# mcu_v03.net
KiCad netlist of a schematic drawn in EAGLE
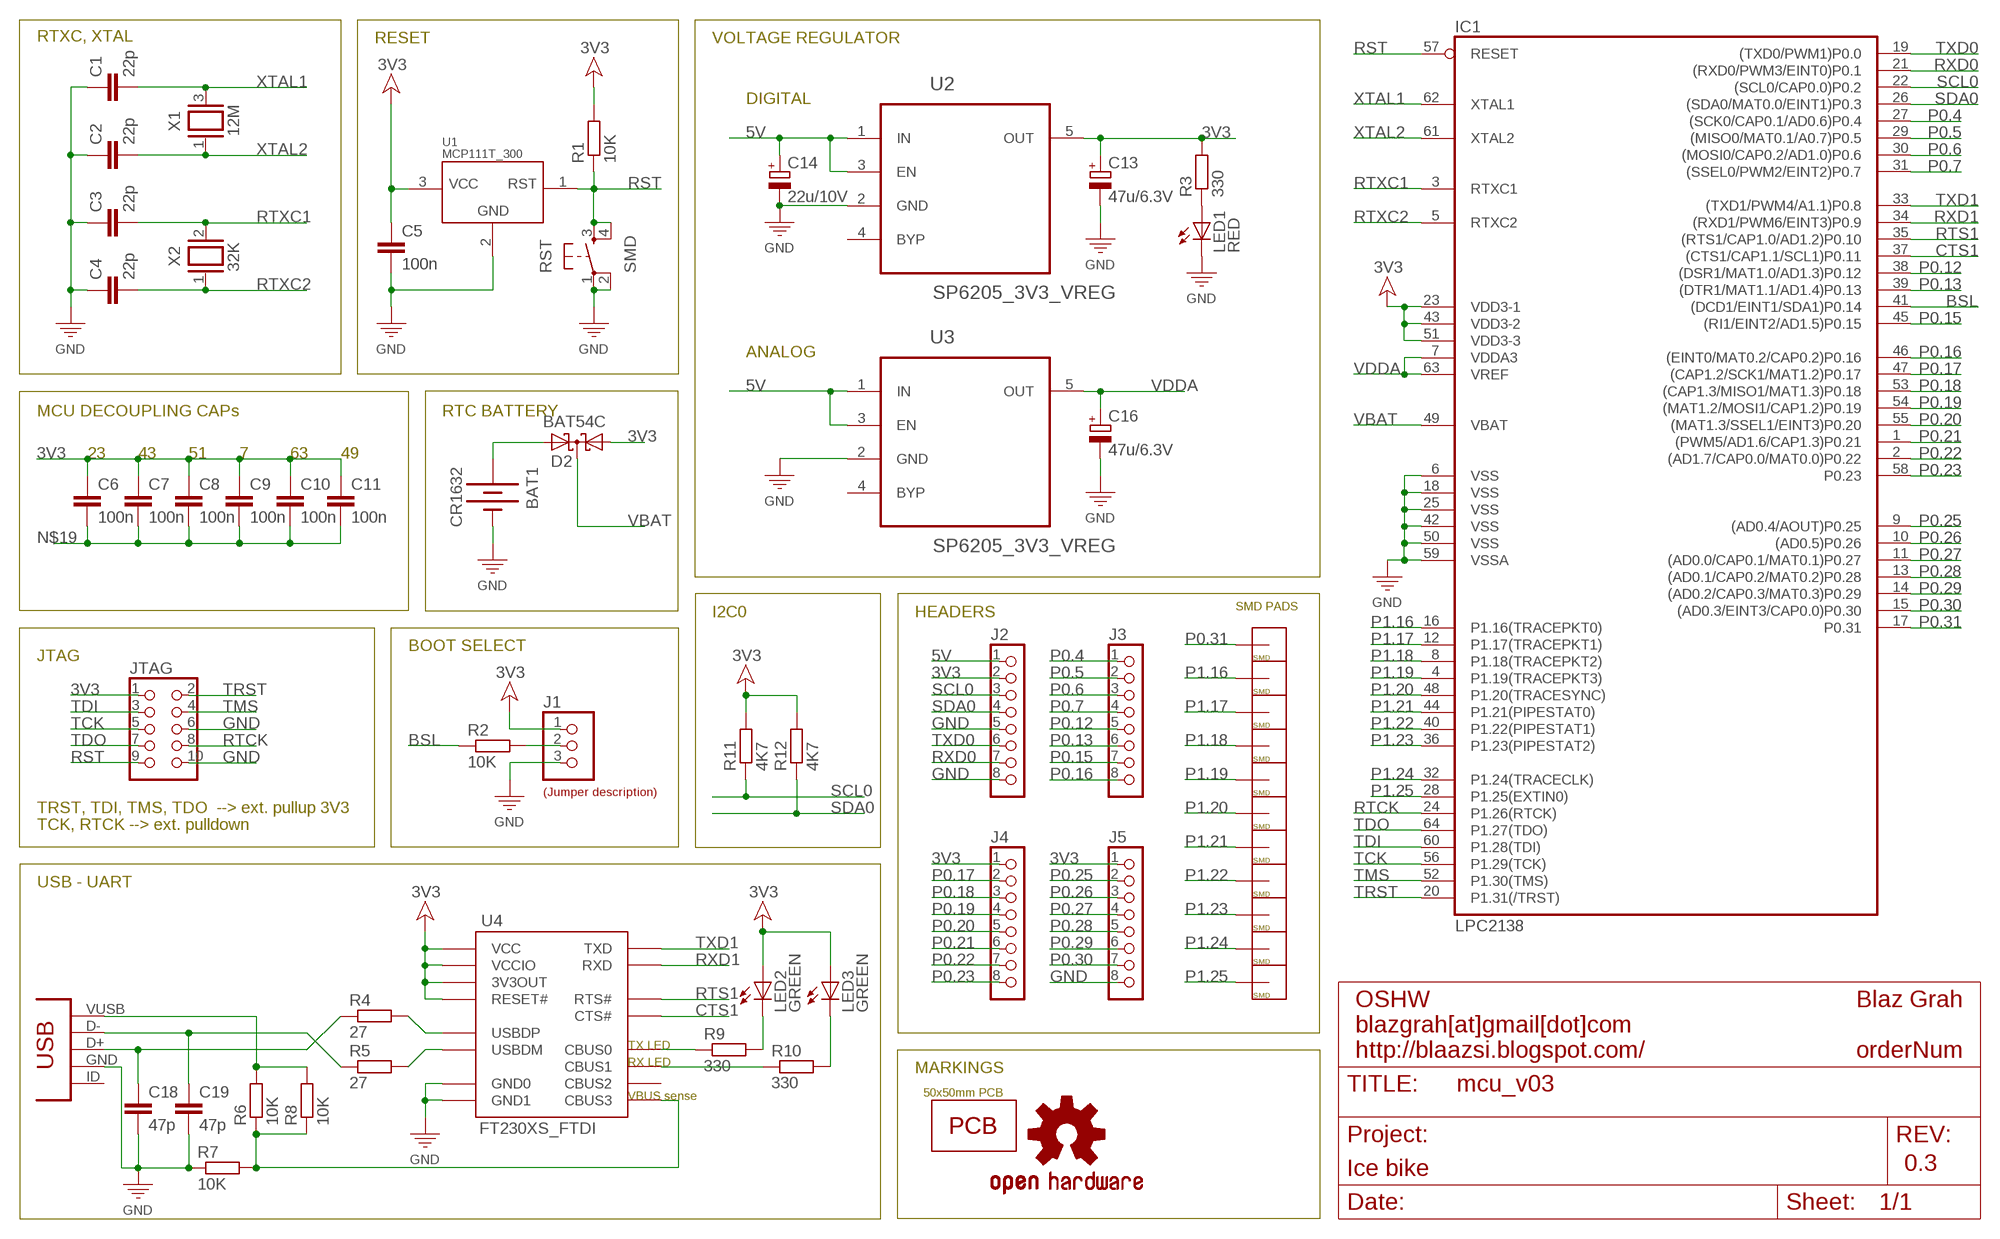
[diagram p0: schematic, sheet 1]

(export (version "E")
  (design (tool "Eeschema 10.0.6"))
  (components
    (comp (ref "BAT1")
      (value "CR1632")
      (footprint "eagle-import:BATTERY_16MM_SDM")
      (libsource (lib "eagle-import") (part "BATTERY"))
    )
    (comp (ref "C1")
      (value "22p")
      (footprint "eagle-import:C0603")
      (libsource (lib "eagle-import") (part "C-EUC0603"))
    )
    (comp (ref "C2")
      (value "22p")
      (footprint "eagle-import:C0603")
      (libsource (lib "eagle-import") (part "C-EUC0603"))
    )
    (comp (ref "C3")
      (value "22p")
      (footprint "eagle-import:C0603")
      (libsource (lib "eagle-import") (part "C-EUC0603"))
    )
    (comp (ref "C4")
      (value "22p")
      (footprint "eagle-import:C0603")
      (libsource (lib "eagle-import") (part "C-EUC0603"))
    )
    (comp (ref "C5")
      (value "100n")
      (footprint "eagle-import:C0603")
      (libsource (lib "eagle-import") (part "C-EUC0603"))
    )
    (comp (ref "C6")
      (value "100n")
      (footprint "eagle-import:C0603")
      (libsource (lib "eagle-import") (part "C-EUC0603"))
    )
    (comp (ref "C7")
      (value "100n")
      (footprint "eagle-import:C0603")
      (libsource (lib "eagle-import") (part "C-EUC0603"))
    )
    (comp (ref "C8")
      (value "100n")
      (footprint "eagle-import:C0603")
      (libsource (lib "eagle-import") (part "C-EUC0603"))
    )
    (comp (ref "C9")
      (value "100n")
      (footprint "eagle-import:C0603")
      (libsource (lib "eagle-import") (part "C-EUC0603"))
    )
    (comp (ref "C10")
      (value "100n")
      (footprint "eagle-import:C0603")
      (libsource (lib "eagle-import") (part "C-EUC0603"))
    )
    (comp (ref "C11")
      (value "100n")
      (footprint "eagle-import:C0603")
      (libsource (lib "eagle-import") (part "C-EUC0603"))
    )
    (comp (ref "C13")
      (value "47u/6.3V")
      (footprint "eagle-import:SMC_B")
      (libsource (lib "eagle-import") (part "CAPACITOR_POL-SMC_B"))
    )
    (comp (ref "C14")
      (value "22u/10V")
      (footprint "eagle-import:SMC_B")
      (libsource (lib "eagle-import") (part "CAPACITOR_POL-SMC_B"))
    )
    (comp (ref "C16")
      (value "47u/6.3V")
      (footprint "eagle-import:SMC_B")
      (libsource (lib "eagle-import") (part "CAPACITOR_POL-SMC_B"))
    )
    (comp (ref "C18")
      (value "47p")
      (footprint "eagle-import:C0603")
      (libsource (lib "eagle-import") (part "C-EUC0603"))
    )
    (comp (ref "C19")
      (value "47p")
      (footprint "eagle-import:C0603")
      (libsource (lib "eagle-import") (part "C-EUC0603"))
    )
    (comp (ref "D2")
      (value "BAT54C")
      (footprint "eagle-import:SOT23")
      (libsource (lib "eagle-import") (part "BAT54C"))
    )
    (comp (ref "IC1")
      (value "LPC2138")
      (footprint "eagle-import:LQFP64")
      (libsource (lib "eagle-import") (part "LCP2138_LQFP64"))
    )
    (comp (ref "J1")
      (value "JUMPER_1X3ALT")
      (footprint "eagle-import:JUMPER_SOLDER")
      (libsource (lib "eagle-import") (part "JUMPER_1X3ALT"))
    )
    (comp (ref "J2")
      (value "CON_HEADER_1X08-PTH")
      (footprint "eagle-import:M1X8")
      (libsource (lib "eagle-import") (part "CON_HEADER_1X08-PTH"))
    )
    (comp (ref "J3")
      (value "CON_HEADER_1X08-PTH")
      (footprint "eagle-import:M1X8")
      (libsource (lib "eagle-import") (part "CON_HEADER_1X08-PTH"))
    )
    (comp (ref "J4")
      (value "CON_HEADER_1X08-PTH")
      (footprint "eagle-import:M1X8")
      (libsource (lib "eagle-import") (part "CON_HEADER_1X08-PTH"))
    )
    (comp (ref "J5")
      (value "CON_HEADER_1X08-PTH")
      (footprint "eagle-import:M1X8")
      (libsource (lib "eagle-import") (part "CON_HEADER_1X08-PTH"))
    )
    (comp (ref "JTAG")
      (value "CON_HEADER_2X05-PTH+SHROUDED_A")
      (footprint "eagle-import:PINSHRD_PTH_2X05")
      (libsource (lib "eagle-import") (part "CON_HEADER_2X05-PTH+SHROUDED_A"))
    )
    (comp (ref "LED1")
      (value "RED")
      (footprint "eagle-import:LED-0603")
      (libsource (lib "eagle-import") (part "LED0603"))
    )
    (comp (ref "LED2")
      (value "GREEN")
      (footprint "eagle-import:LED-0603")
      (libsource (lib "eagle-import") (part "LED0603"))
    )
    (comp (ref "LED3")
      (value "GREEN")
      (footprint "eagle-import:LED-0603")
      (libsource (lib "eagle-import") (part "LED0603"))
    )
    (comp (ref "PCB1")
      (value "PCB_DP_SQUARE-5X5")
      (footprint "eagle-import:PCB5X5")
      (libsource (lib "eagle-import") (part "PCB_DP_SQUARE-5X5"))
    )
    (comp (ref "R1")
      (value "10K")
      (footprint "eagle-import:R0603")
      (libsource (lib "eagle-import") (part "R-EU0603"))
    )
    (comp (ref "R2")
      (value "10K")
      (footprint "eagle-import:R0603")
      (libsource (lib "eagle-import") (part "R-EU0603"))
    )
    (comp (ref "R3")
      (value "330")
      (footprint "eagle-import:R0603")
      (libsource (lib "eagle-import") (part "R-EU0603"))
    )
    (comp (ref "R4")
      (value "27")
      (footprint "eagle-import:R0603")
      (libsource (lib "eagle-import") (part "R-EU0603"))
    )
    (comp (ref "R5")
      (value "27")
      (footprint "eagle-import:R0603")
      (libsource (lib "eagle-import") (part "R-EU0603"))
    )
    (comp (ref "R6")
      (value "10K")
      (footprint "eagle-import:R0603")
      (libsource (lib "eagle-import") (part "R-EU0603"))
    )
    (comp (ref "R7")
      (value "10K")
      (footprint "eagle-import:R0603")
      (libsource (lib "eagle-import") (part "R-EU0603"))
    )
    (comp (ref "R8")
      (value "10K")
      (footprint "eagle-import:R0603")
      (libsource (lib "eagle-import") (part "R-EU0603"))
    )
    (comp (ref "R9")
      (value "330")
      (footprint "eagle-import:R0603")
      (libsource (lib "eagle-import") (part "R-EU0603"))
    )
    (comp (ref "R10")
      (value "330")
      (footprint "eagle-import:R0603")
      (libsource (lib "eagle-import") (part "R-EU0603"))
    )
    (comp (ref "R11")
      (value "4K7")
      (footprint "eagle-import:R0603")
      (libsource (lib "eagle-import") (part "R-EU0603"))
    )
    (comp (ref "R12")
      (value "4K7")
      (footprint "eagle-import:R0603")
      (libsource (lib "eagle-import") (part "R-EU0603"))
    )
    (comp (ref "RST")
      (value "SMD")
      (footprint "eagle-import:BUTTON_SW_4P_SMD")
      (libsource (lib "eagle-import") (part "TACTIL_BUTTON"))
    )
    (comp (ref "U$11")
      (value "LABEL_JUMPER_1X3")
      (footprint "eagle-import:JUMP3_DESC")
      (fields (field (name "LEFT") "USER") (field (name "RIGHT") "BOOT"))
      (libsource (lib "eagle-import") (part "LABEL_JUMPER_1X3"))
    )
    (comp (ref "U$13")
      (value "FRAME_DINA4_L")
      (footprint "eagle-import:DP_LOGO")
      (fields
        (field (name "AUTHOR") "Blaz Grah")
        (field (name "LICENSE") "OSHW")
        (field (name "PROJECT") "Ice bike")
        (field (name "REV") "0.3")
        (field (name "URL1") "blazgrah[at]gmail[dot]com")
        (field (name "URL2") "http://blaazsi.blogspot.com/")
      )
      (libsource (lib "eagle-import") (part "FRAME_DINA4_L"))
    )
    (comp (ref "U$17")
      (value "OSHW-LOGOS")
      (footprint "eagle-import:OSHW-LOGO-S")
      (libsource (lib "eagle-import") (part "OSHW-LOGOS"))
    )
    (comp (ref "U$28")
      (value "CON_SMD_PAD_1X1")
      (footprint "eagle-import:CON_SMD_PAD_1_")
      (libsource (lib "eagle-import") (part "CON_SMD_PAD_1X1"))
    )
    (comp (ref "U$29")
      (value "CON_SMD_PAD_1X1")
      (footprint "eagle-import:CON_SMD_PAD_1_")
      (libsource (lib "eagle-import") (part "CON_SMD_PAD_1X1"))
    )
    (comp (ref "U$30")
      (value "CON_SMD_PAD_1X1")
      (footprint "eagle-import:CON_SMD_PAD_1_")
      (libsource (lib "eagle-import") (part "CON_SMD_PAD_1X1"))
    )
    (comp (ref "U$31")
      (value "CON_SMD_PAD_1X1")
      (footprint "eagle-import:CON_SMD_PAD_1_")
      (libsource (lib "eagle-import") (part "CON_SMD_PAD_1X1"))
    )
    (comp (ref "U$32")
      (value "CON_SMD_PAD_1X1")
      (footprint "eagle-import:CON_SMD_PAD_1_")
      (libsource (lib "eagle-import") (part "CON_SMD_PAD_1X1"))
    )
    (comp (ref "U$33")
      (value "CON_SMD_PAD_1X1")
      (footprint "eagle-import:CON_SMD_PAD_1_")
      (libsource (lib "eagle-import") (part "CON_SMD_PAD_1X1"))
    )
    (comp (ref "U$34")
      (value "CON_SMD_PAD_1X1")
      (footprint "eagle-import:CON_SMD_PAD_1_")
      (libsource (lib "eagle-import") (part "CON_SMD_PAD_1X1"))
    )
    (comp (ref "U$35")
      (value "CON_SMD_PAD_1X1")
      (footprint "eagle-import:CON_SMD_PAD_1_")
      (libsource (lib "eagle-import") (part "CON_SMD_PAD_1X1"))
    )
    (comp (ref "U$36")
      (value "CON_SMD_PAD_1X1")
      (footprint "eagle-import:CON_SMD_PAD_1_")
      (libsource (lib "eagle-import") (part "CON_SMD_PAD_1X1"))
    )
    (comp (ref "U$37")
      (value "CON_SMD_PAD_1X1")
      (footprint "eagle-import:CON_SMD_PAD_1_")
      (libsource (lib "eagle-import") (part "CON_SMD_PAD_1X1"))
    )
    (comp (ref "U$38")
      (value "CON_SMD_PAD_1X1")
      (footprint "eagle-import:CON_SMD_PAD_1_")
      (libsource (lib "eagle-import") (part "CON_SMD_PAD_1X1"))
    )
    (comp (ref "U1")
      (value "MCP111T_300")
      (footprint "eagle-import:SOT23")
      (libsource (lib "eagle-import") (part "MCP111T_300"))
    )
    (comp (ref "U2")
      (value "SP6205_3V3_VREG")
      (footprint "eagle-import:SOT23-5")
      (libsource (lib "eagle-import") (part "SP6205_3V3_VREG"))
    )
    (comp (ref "U3")
      (value "SP6205_3V3_VREG")
      (footprint "eagle-import:SOT23-5")
      (libsource (lib "eagle-import") (part "SP6205_3V3_VREG"))
    )
    (comp (ref "U4")
      (value "FT230XS_FTDI")
      (footprint "eagle-import:SSOP16")
      (libsource (lib "eagle-import") (part "FT230XS_FTDI"))
    )
    (comp (ref "USB1")
      (value "CON-USB-F-MINI-B")
      (footprint "eagle-import:CONN_USB_MINI-B")
      (libsource (lib "eagle-import") (part "CON-USB-F-MINI-B"))
    )
    (comp (ref "X1")
      (value "12M")
      (footprint "eagle-import:ABMM2_6X3.6")
      (libsource (lib "eagle-import") (part "CRYSTAL12MHZ"))
    )
    (comp (ref "X2")
      (value "32K")
      (footprint "eagle-import:ABS10_4.9X1.8")
      (libsource (lib "eagle-import") (part "CRYSTAL32KHZ"))
    )
  )
  (nets
    (net (code "1") (name "/5V") (class "Default")
      (node (ref "C14") (pin "+") (pinfunction "+_+") (pintype "passive"))
      (node (ref "J2") (pin "1") (pinfunction "1_1") (pintype "passive"))
      (node (ref "U2") (pin "1") (pinfunction "IN_1") (pintype "input"))
      (node (ref "U2") (pin "3") (pinfunction "EN_3") (pintype "input"))
      (node (ref "U3") (pin "1") (pinfunction "IN_1") (pintype "input"))
      (node (ref "U3") (pin "3") (pinfunction "EN_3") (pintype "input"))
    )
    (net (code "2") (name "/BSL") (class "Default")
      (node (ref "IC1") (pin "41") (pinfunction "(DCD1/EINT1/SDA1)P0.14_41") (pintype "bidirectional"))
      (node (ref "R2") (pin "1") (pinfunction "1_1") (pintype "passive"))
    )
    (net (code "3") (name "/CTS1") (class "Default")
      (node (ref "IC1") (pin "37") (pinfunction "(CTS1/CAP1.1/SCL1)P0.11_37") (pintype "bidirectional"))
      (node (ref "U4") (pin "P$6") (pinfunction "CTS#_P$6") (pintype "bidirectional"))
    )
    (net (code "4") (name "/N$19") (class "Default")
      (node (ref "C10") (pin "2") (pinfunction "2_2") (pintype "passive"))
      (node (ref "C11") (pin "2") (pinfunction "2_2") (pintype "passive"))
      (node (ref "C6") (pin "2") (pinfunction "2_2") (pintype "passive"))
      (node (ref "C7") (pin "2") (pinfunction "2_2") (pintype "passive"))
      (node (ref "C8") (pin "2") (pinfunction "2_2") (pintype "passive"))
      (node (ref "C9") (pin "2") (pinfunction "2_2") (pintype "passive"))
    )
    (net (code "5") (name "/P0.4") (class "Default")
      (node (ref "IC1") (pin "27") (pinfunction "(SCK0/CAP0.1/AD0.6)P0.4_27") (pintype "bidirectional"))
      (node (ref "J3") (pin "1") (pinfunction "1_1") (pintype "passive"))
    )
    (net (code "6") (name "/P0.5") (class "Default")
      (node (ref "IC1") (pin "29") (pinfunction "(MISO0/MAT0.1/A0.7)P0.5_29") (pintype "bidirectional"))
      (node (ref "J3") (pin "2") (pinfunction "2_2") (pintype "passive"))
    )
    (net (code "7") (name "/P0.6") (class "Default")
      (node (ref "IC1") (pin "30") (pinfunction "(MOSI0/CAP0.2/AD1.0)P0.6_30") (pintype "bidirectional"))
      (node (ref "J3") (pin "3") (pinfunction "3_3") (pintype "passive"))
    )
    (net (code "8") (name "/P0.7") (class "Default")
      (node (ref "IC1") (pin "31") (pinfunction "(SSEL0/PWM2/EINT2)P0.7_31") (pintype "bidirectional"))
      (node (ref "J3") (pin "4") (pinfunction "4_4") (pintype "passive"))
    )
    (net (code "9") (name "/P0.12") (class "Default")
      (node (ref "IC1") (pin "38") (pinfunction "(DSR1/MAT1.0/AD1.3)P0.12_38") (pintype "bidirectional"))
      (node (ref "J3") (pin "5") (pinfunction "5_5") (pintype "passive"))
    )
    (net (code "10") (name "/P0.13") (class "Default")
      (node (ref "IC1") (pin "39") (pinfunction "(DTR1/MAT1.1/AD1.4)P0.13_39") (pintype "bidirectional"))
      (node (ref "J3") (pin "6") (pinfunction "6_6") (pintype "passive"))
    )
    (net (code "11") (name "/P0.15") (class "Default")
      (node (ref "IC1") (pin "45") (pinfunction "(RI1/EINT2/AD1.5)P0.15_45") (pintype "bidirectional"))
      (node (ref "J3") (pin "7") (pinfunction "7_7") (pintype "passive"))
    )
    (net (code "12") (name "/P0.16") (class "Default")
      (node (ref "IC1") (pin "46") (pinfunction "(EINT0/MAT0.2/CAP0.2)P0.16_46") (pintype "bidirectional"))
      (node (ref "J3") (pin "8") (pinfunction "8_8") (pintype "passive"))
    )
    (net (code "13") (name "/P0.17") (class "Default")
      (node (ref "IC1") (pin "47") (pinfunction "(CAP1.2/SCK1/MAT1.2)P0.17_47") (pintype "bidirectional"))
      (node (ref "J4") (pin "2") (pinfunction "2_2") (pintype "passive"))
    )
    (net (code "14") (name "/P0.18") (class "Default")
      (node (ref "IC1") (pin "53") (pinfunction "(CAP1.3/MISO1/MAT1.3)P0.18_53") (pintype "bidirectional"))
      (node (ref "J4") (pin "3") (pinfunction "3_3") (pintype "passive"))
    )
    (net (code "15") (name "/P0.19") (class "Default")
      (node (ref "IC1") (pin "54") (pinfunction "(MAT1.2/MOSI1/CAP1.2)P0.19_54") (pintype "bidirectional"))
      (node (ref "J4") (pin "4") (pinfunction "4_4") (pintype "passive"))
    )
    (net (code "16") (name "/P0.20") (class "Default")
      (node (ref "IC1") (pin "55") (pinfunction "(MAT1.3/SSEL1/EINT3)P0.20_55") (pintype "bidirectional"))
      (node (ref "J4") (pin "5") (pinfunction "5_5") (pintype "passive"))
    )
    (net (code "17") (name "/P0.21") (class "Default")
      (node (ref "IC1") (pin "1") (pinfunction "(PWM5/AD1.6/CAP1.3)P0.21_1") (pintype "bidirectional"))
      (node (ref "J4") (pin "6") (pinfunction "6_6") (pintype "passive"))
    )
    (net (code "18") (name "/P0.22") (class "Default")
      (node (ref "IC1") (pin "2") (pinfunction "(AD1.7/CAP0.0/MAT0.0)P0.22_2") (pintype "bidirectional"))
      (node (ref "J4") (pin "7") (pinfunction "7_7") (pintype "passive"))
    )
    (net (code "19") (name "/P0.23") (class "Default")
      (node (ref "IC1") (pin "58") (pinfunction "P0.23_58") (pintype "bidirectional"))
      (node (ref "J4") (pin "8") (pinfunction "8_8") (pintype "passive"))
    )
    (net (code "20") (name "/P0.25") (class "Default")
      (node (ref "IC1") (pin "9") (pinfunction "(AD0.4/AOUT)P0.25_9") (pintype "bidirectional"))
      (node (ref "J5") (pin "2") (pinfunction "2_2") (pintype "passive"))
    )
    (net (code "21") (name "/P0.26") (class "Default")
      (node (ref "IC1") (pin "10") (pinfunction "(AD0.5)P0.26_10") (pintype "bidirectional"))
      (node (ref "J5") (pin "3") (pinfunction "3_3") (pintype "passive"))
    )
    (net (code "22") (name "/P0.27") (class "Default")
      (node (ref "IC1") (pin "11") (pinfunction "(AD0.0/CAP0.1/MAT0.1)P0.27_11") (pintype "bidirectional"))
      (node (ref "J5") (pin "4") (pinfunction "4_4") (pintype "passive"))
    )
    (net (code "23") (name "/P0.28") (class "Default")
      (node (ref "IC1") (pin "13") (pinfunction "(AD0.1/CAP0.2/MAT0.2)P0.28_13") (pintype "bidirectional"))
      (node (ref "J5") (pin "5") (pinfunction "5_5") (pintype "passive"))
    )
    (net (code "24") (name "/P0.29") (class "Default")
      (node (ref "IC1") (pin "14") (pinfunction "(AD0.2/CAP0.3/MAT0.3)P0.29_14") (pintype "bidirectional"))
      (node (ref "J5") (pin "6") (pinfunction "6_6") (pintype "passive"))
    )
    (net (code "25") (name "/P0.30") (class "Default")
      (node (ref "IC1") (pin "15") (pinfunction "(AD0.3/EINT3/CAP0.0)P0.30_15") (pintype "bidirectional"))
      (node (ref "J5") (pin "7") (pinfunction "7_7") (pintype "passive"))
    )
    (net (code "26") (name "/P0.31") (class "Default")
      (node (ref "IC1") (pin "17") (pinfunction "P0.31_17") (pintype "output"))
      (node (ref "U$38") (pin "1") (pinfunction "1_1") (pintype "bidirectional"))
    )
    (net (code "27") (name "/P1.16") (class "Default")
      (node (ref "IC1") (pin "16") (pinfunction "P1.16(TRACEPKT0)_16") (pintype "bidirectional"))
      (node (ref "U$28") (pin "1") (pinfunction "1_1") (pintype "bidirectional"))
    )
    (net (code "28") (name "/P1.17") (class "Default")
      (node (ref "IC1") (pin "12") (pinfunction "P1.17(TRACEPKT1)_12") (pintype "bidirectional"))
      (node (ref "U$29") (pin "1") (pinfunction "1_1") (pintype "bidirectional"))
    )
    (net (code "29") (name "/P1.18") (class "Default")
      (node (ref "IC1") (pin "8") (pinfunction "P1.18(TRACEPKT2)_8") (pintype "bidirectional"))
      (node (ref "U$30") (pin "1") (pinfunction "1_1") (pintype "bidirectional"))
    )
    (net (code "30") (name "/P1.19") (class "Default")
      (node (ref "IC1") (pin "4") (pinfunction "P1.19(TRACEPKT3)_4") (pintype "bidirectional"))
      (node (ref "U$31") (pin "1") (pinfunction "1_1") (pintype "bidirectional"))
    )
    (net (code "31") (name "/P1.20") (class "Default")
      (node (ref "IC1") (pin "48") (pinfunction "P1.20(TRACESYNC)_48") (pintype "bidirectional"))
      (node (ref "U$32") (pin "1") (pinfunction "1_1") (pintype "bidirectional"))
    )
    (net (code "32") (name "/P1.21") (class "Default")
      (node (ref "IC1") (pin "44") (pinfunction "P1.21(PIPESTAT0)_44") (pintype "bidirectional"))
      (node (ref "U$33") (pin "1") (pinfunction "1_1") (pintype "bidirectional"))
    )
    (net (code "33") (name "/P1.22") (class "Default")
      (node (ref "IC1") (pin "40") (pinfunction "P1.22(PIPESTAT1)_40") (pintype "bidirectional"))
      (node (ref "U$34") (pin "1") (pinfunction "1_1") (pintype "bidirectional"))
    )
    (net (code "34") (name "/P1.23") (class "Default")
      (node (ref "IC1") (pin "36") (pinfunction "P1.23(PIPESTAT2)_36") (pintype "bidirectional"))
      (node (ref "U$35") (pin "1") (pinfunction "1_1") (pintype "bidirectional"))
    )
    (net (code "35") (name "/P1.24") (class "Default")
      (node (ref "IC1") (pin "32") (pinfunction "P1.24(TRACECLK)_32") (pintype "bidirectional"))
      (node (ref "U$36") (pin "1") (pinfunction "1_1") (pintype "bidirectional"))
    )
    (net (code "36") (name "/P1.25") (class "Default")
      (node (ref "IC1") (pin "28") (pinfunction "P1.25(EXTIN0)_28") (pintype "bidirectional"))
      (node (ref "U$37") (pin "1") (pinfunction "1_1") (pintype "bidirectional"))
    )
    (net (code "37") (name "/RST") (class "Default")
      (node (ref "IC1") (pin "57") (pinfunction "RESET_57") (pintype "input"))
      (node (ref "JTAG") (pin "9") (pinfunction "9_9") (pintype "passive"))
      (node (ref "R1") (pin "1") (pinfunction "1_1") (pintype "passive"))
      (node (ref "RST") (pin "3") (pinfunction "3_3") (pintype "passive"))
      (node (ref "RST") (pin "4") (pinfunction "4_4") (pintype "passive"))
      (node (ref "U1") (pin "1") (pinfunction "RST_1") (pintype "output"))
    )
    (net (code "38") (name "/RTCK") (class "Default")
      (node (ref "IC1") (pin "24") (pinfunction "P1.26(RTCK)_24") (pintype "bidirectional"))
      (node (ref "JTAG") (pin "8") (pinfunction "8_8") (pintype "passive"))
    )
    (net (code "39") (name "/RTS1") (class "Default")
      (node (ref "IC1") (pin "35") (pinfunction "(RTS1/CAP1.0/AD1.2)P0.10_35") (pintype "bidirectional"))
      (node (ref "U4") (pin "P$2") (pinfunction "RTS#_P$2") (pintype "bidirectional"))
    )
    (net (code "40") (name "/RTXC1") (class "Default")
      (node (ref "C3") (pin "2") (pinfunction "2_2") (pintype "passive"))
      (node (ref "IC1") (pin "3") (pinfunction "RTXC1_3") (pintype "input"))
      (node (ref "X2") (pin "2") (pinfunction "2_2") (pintype "passive"))
    )
    (net (code "41") (name "/RTXC2") (class "Default")
      (node (ref "C4") (pin "2") (pinfunction "2_2") (pintype "passive"))
      (node (ref "IC1") (pin "5") (pinfunction "RTXC2_5") (pintype "output"))
      (node (ref "X2") (pin "1") (pinfunction "1_1") (pintype "passive"))
    )
    (net (code "42") (name "/RXD0") (class "Default")
      (node (ref "IC1") (pin "21") (pinfunction "(RXD0/PWM3/EINT0)P0.1_21") (pintype "bidirectional"))
      (node (ref "J2") (pin "7") (pinfunction "7_7") (pintype "passive"))
    )
    (net (code "43") (name "/RXD1") (class "Default")
      (node (ref "IC1") (pin "34") (pinfunction "(RXD1/PWM6/EINT3)P0.9_34") (pintype "bidirectional"))
      (node (ref "U4") (pin "P$4") (pinfunction "RXD_P$4") (pintype "bidirectional"))
    )
    (net (code "44") (name "/SCL0") (class "Default")
      (node (ref "IC1") (pin "22") (pinfunction "(SCL0/CAP0.0)P0.2_22") (pintype "bidirectional"))
      (node (ref "J2") (pin "3") (pinfunction "3_3") (pintype "passive"))
      (node (ref "R11") (pin "1") (pinfunction "1_1") (pintype "passive"))
    )
    (net (code "45") (name "/SDA0") (class "Default")
      (node (ref "IC1") (pin "26") (pinfunction "(SDA0/MAT0.0/EINT1)P0.3_26") (pintype "bidirectional"))
      (node (ref "J2") (pin "4") (pinfunction "4_4") (pintype "passive"))
      (node (ref "R12") (pin "1") (pinfunction "1_1") (pintype "passive"))
    )
    (net (code "46") (name "/TCK") (class "Default")
      (node (ref "IC1") (pin "56") (pinfunction "P1.29(TCK)_56") (pintype "bidirectional"))
      (node (ref "JTAG") (pin "5") (pinfunction "5_5") (pintype "passive"))
    )
    (net (code "47") (name "/TDI") (class "Default")
      (node (ref "IC1") (pin "60") (pinfunction "P1.28(TDI)_60") (pintype "bidirectional"))
      (node (ref "JTAG") (pin "3") (pinfunction "3_3") (pintype "passive"))
    )
    (net (code "48") (name "/TDO") (class "Default")
      (node (ref "IC1") (pin "64") (pinfunction "P1.27(TDO)_64") (pintype "bidirectional"))
      (node (ref "JTAG") (pin "7") (pinfunction "7_7") (pintype "passive"))
    )
    (net (code "49") (name "/TMS") (class "Default")
      (node (ref "IC1") (pin "52") (pinfunction "P1.30(TMS)_52") (pintype "bidirectional"))
      (node (ref "JTAG") (pin "4") (pinfunction "4_4") (pintype "passive"))
    )
    (net (code "50") (name "/TRST") (class "Default")
      (node (ref "IC1") (pin "20") (pinfunction "P1.31(/TRST)_20") (pintype "bidirectional"))
      (node (ref "JTAG") (pin "2") (pinfunction "2_2") (pintype "passive"))
    )
    (net (code "51") (name "/TXD0") (class "Default")
      (node (ref "IC1") (pin "19") (pinfunction "(TXD0/PWM1)P0.0_19") (pintype "bidirectional"))
      (node (ref "J2") (pin "6") (pinfunction "6_6") (pintype "passive"))
    )
    (net (code "52") (name "/TXD1") (class "Default")
      (node (ref "IC1") (pin "33") (pinfunction "(TXD1/PWM4/A1.1)P0.8_33") (pintype "bidirectional"))
      (node (ref "U4") (pin "P$1") (pinfunction "TXD_P$1") (pintype "bidirectional"))
    )
    (net (code "53") (name "/VBAT") (class "Default")
      (node (ref "D2") (pin "3") (pinfunction "CC_3") (pintype "passive"))
      (node (ref "IC1") (pin "49") (pinfunction "VBAT_49") (pintype "power_in"))
    )
    (net (code "54") (name "/VDDA") (class "Default")
      (node (ref "C16") (pin "+") (pinfunction "+_+") (pintype "passive"))
      (node (ref "IC1") (pin "63") (pinfunction "VREF_63") (pintype "input"))
      (node (ref "IC1") (pin "7") (pinfunction "VDDA3_7") (pintype "power_in"))
      (node (ref "U3") (pin "5") (pinfunction "OUT_5") (pintype "power_in"))
    )
    (net (code "55") (name "/XTAL1") (class "Default")
      (node (ref "C1") (pin "2") (pinfunction "2_2") (pintype "passive"))
      (node (ref "IC1") (pin "62") (pinfunction "XTAL1_62") (pintype "input"))
      (node (ref "X1") (pin "3") (pinfunction "2_3") (pintype "passive"))
    )
    (net (code "56") (name "/XTAL2") (class "Default")
      (node (ref "C2") (pin "2") (pinfunction "2_2") (pintype "passive"))
      (node (ref "IC1") (pin "61") (pinfunction "XTAL2_61") (pintype "output"))
      (node (ref "X1") (pin "1") (pinfunction "1_1") (pintype "passive"))
    )
    (net (code "57") (name "3V3") (class "Default")
      (node (ref "C10") (pin "1") (pinfunction "1_1") (pintype "passive"))
      (node (ref "C11") (pin "1") (pinfunction "1_1") (pintype "passive"))
      (node (ref "C13") (pin "+") (pinfunction "+_+") (pintype "passive"))
      (node (ref "C5") (pin "1") (pinfunction "1_1") (pintype "passive"))
      (node (ref "C6") (pin "1") (pinfunction "1_1") (pintype "passive"))
      (node (ref "C7") (pin "1") (pinfunction "1_1") (pintype "passive"))
      (node (ref "C8") (pin "1") (pinfunction "1_1") (pintype "passive"))
      (node (ref "C9") (pin "1") (pinfunction "1_1") (pintype "passive"))
      (node (ref "D2") (pin "1") (pinfunction "A1_1") (pintype "passive"))
      (node (ref "IC1") (pin "23") (pinfunction "VDD3-1_23") (pintype "power_in"))
      (node (ref "IC1") (pin "43") (pinfunction "VDD3-2_43") (pintype "power_in"))
      (node (ref "IC1") (pin "51") (pinfunction "VDD3-3_51") (pintype "power_in"))
      (node (ref "J1") (pin "1") (pinfunction "1_1") (pintype "passive"))
      (node (ref "J2") (pin "2") (pinfunction "2_2") (pintype "passive"))
      (node (ref "J4") (pin "1") (pinfunction "1_1") (pintype "passive"))
      (node (ref "J5") (pin "1") (pinfunction "1_1") (pintype "passive"))
      (node (ref "JTAG") (pin "1") (pinfunction "1_1") (pintype "passive"))
      (node (ref "LED2") (pin "A") (pinfunction "A_A") (pintype "passive"))
      (node (ref "LED3") (pin "A") (pinfunction "A_A") (pintype "passive"))
      (node (ref "R1") (pin "2") (pinfunction "2_2") (pintype "passive"))
      (node (ref "R11") (pin "2") (pinfunction "2_2") (pintype "passive"))
      (node (ref "R12") (pin "2") (pinfunction "2_2") (pintype "passive"))
      (node (ref "R3") (pin "2") (pinfunction "2_2") (pintype "passive"))
      (node (ref "U1") (pin "3") (pinfunction "VCC_3") (pintype "input"))
      (node (ref "U2") (pin "5") (pinfunction "OUT_5") (pintype "power_in"))
      (node (ref "U4") (pin "P$10") (pinfunction "3V3OUT_P$10") (pintype "power_in"))
      (node (ref "U4") (pin "P$11") (pinfunction "RESET#_P$11") (pintype "bidirectional"))
      (node (ref "U4") (pin "P$12") (pinfunction "VCC_P$12") (pintype "power_in"))
      (node (ref "U4") (pin "P$3") (pinfunction "VCCIO_P$3") (pintype "power_in"))
    )
    (net (code "58") (name "GND") (class "Default")
      (node (ref "BAT1") (pin "NEG") (pinfunction "NEG_NEG") (pintype "power_in"))
      (node (ref "C1") (pin "1") (pinfunction "1_1") (pintype "passive"))
      (node (ref "C13") (pin "-") (pinfunction "-_-") (pintype "passive"))
      (node (ref "C14") (pin "-") (pinfunction "-_-") (pintype "passive"))
      (node (ref "C16") (pin "-") (pinfunction "-_-") (pintype "passive"))
      (node (ref "C18") (pin "2") (pinfunction "2_2") (pintype "passive"))
      (node (ref "C19") (pin "2") (pinfunction "2_2") (pintype "passive"))
      (node (ref "C2") (pin "1") (pinfunction "1_1") (pintype "passive"))
      (node (ref "C3") (pin "1") (pinfunction "1_1") (pintype "passive"))
      (node (ref "C4") (pin "1") (pinfunction "1_1") (pintype "passive"))
      (node (ref "C5") (pin "2") (pinfunction "2_2") (pintype "passive"))
      (node (ref "IC1") (pin "18") (pinfunction "VSS_18") (pintype "power_in"))
      (node (ref "IC1") (pin "25") (pinfunction "VSS_25") (pintype "power_in"))
      (node (ref "IC1") (pin "42") (pinfunction "VSS_42") (pintype "power_in"))
      (node (ref "IC1") (pin "50") (pinfunction "VSS_50") (pintype "power_in"))
      (node (ref "IC1") (pin "59") (pinfunction "VSSA_59") (pintype "power_in"))
      (node (ref "IC1") (pin "6") (pinfunction "VSS_6") (pintype "power_in"))
      (node (ref "J1") (pin "3") (pinfunction "3_3") (pintype "passive"))
      (node (ref "J2") (pin "5") (pinfunction "5_5") (pintype "passive"))
      (node (ref "J2") (pin "8") (pinfunction "8_8") (pintype "passive"))
      (node (ref "J5") (pin "8") (pinfunction "8_8") (pintype "passive"))
      (node (ref "JTAG") (pin "10") (pinfunction "10_10") (pintype "passive"))
      (node (ref "JTAG") (pin "6") (pinfunction "6_6") (pintype "passive"))
      (node (ref "LED1") (pin "C") (pinfunction "C_C") (pintype "passive"))
      (node (ref "R7") (pin "1") (pinfunction "1_1") (pintype "passive"))
      (node (ref "RST") (pin "1") (pinfunction "1_1") (pintype "passive"))
      (node (ref "RST") (pin "2") (pinfunction "2_2") (pintype "passive"))
      (node (ref "U1") (pin "2") (pinfunction "GND_2") (pintype "power_in"))
      (node (ref "U2") (pin "2") (pinfunction "GND_2") (pintype "power_in"))
      (node (ref "U3") (pin "2") (pinfunction "GND_2") (pintype "power_in"))
      (node (ref "U4") (pin "P$13") (pinfunction "GND1_P$13") (pintype "power_in"))
      (node (ref "U4") (pin "P$5") (pinfunction "GND0_P$5") (pintype "power_in"))
      (node (ref "USB1") (pin "GND") (pinfunction "GND_GND") (pintype "bidirectional"))
    )
    (net (code "59") (name "Net-(C18-Pad1)") (class "Default")
      (node (ref "C18") (pin "1") (pinfunction "1_1") (pintype "passive"))
      (node (ref "R4") (pin "1") (pinfunction "1_1") (pintype "passive"))
      (node (ref "USB1") (pin "D+") (pinfunction "D+_D+") (pintype "bidirectional"))
    )
    (net (code "60") (name "Net-(C19-Pad1)") (class "Default")
      (node (ref "C19") (pin "1") (pinfunction "1_1") (pintype "passive"))
      (node (ref "R5") (pin "1") (pinfunction "1_1") (pintype "passive"))
      (node (ref "USB1") (pin "D-") (pinfunction "D-_D-") (pintype "bidirectional"))
    )
    (net (code "61") (name "Net-(D2-A2)") (class "Default")
      (node (ref "BAT1") (pin "POS1") (pinfunction "POZ_POS1") (pintype "power_in"))
      (node (ref "BAT1") (pin "POS2") (pinfunction "POZ_POS2") (pintype "power_in"))
      (node (ref "D2") (pin "2") (pinfunction "A2_2") (pintype "passive"))
    )
    (net (code "62") (name "Net-(J1-Pad2)") (class "Default")
      (node (ref "J1") (pin "2") (pinfunction "2_2") (pintype "passive"))
      (node (ref "R2") (pin "2") (pinfunction "2_2") (pintype "passive"))
    )
    (net (code "63") (name "Net-(LED1-PadA)") (class "Default")
      (node (ref "LED1") (pin "A") (pinfunction "A_A") (pintype "passive"))
      (node (ref "R3") (pin "1") (pinfunction "1_1") (pintype "passive"))
    )
    (net (code "64") (name "Net-(LED2-PadC)") (class "Default")
      (node (ref "LED2") (pin "C") (pinfunction "C_C") (pintype "passive"))
      (node (ref "R9") (pin "2") (pinfunction "2_2") (pintype "passive"))
    )
    (net (code "65") (name "Net-(LED3-PadC)") (class "Default")
      (node (ref "LED3") (pin "C") (pinfunction "C_C") (pintype "passive"))
      (node (ref "R10") (pin "2") (pinfunction "2_2") (pintype "passive"))
    )
    (net (code "66") (name "Net-(R6-Pad2)") (class "Default")
      (node (ref "R6") (pin "2") (pinfunction "2_2") (pintype "passive"))
      (node (ref "R8") (pin "2") (pinfunction "2_2") (pintype "passive"))
      (node (ref "USB1") (pin "VUSB") (pinfunction "VUSB_VUSB") (pintype "bidirectional"))
    )
    (net (code "67") (name "Net-(U4-CBUS0)") (class "Default")
      (node (ref "R9") (pin "1") (pinfunction "1_1") (pintype "passive"))
      (node (ref "U4") (pin "P$15") (pinfunction "CBUS0_P$15") (pintype "bidirectional"))
    )
    (net (code "68") (name "Net-(U4-CBUS1)") (class "Default")
      (node (ref "R10") (pin "1") (pinfunction "1_1") (pintype "passive"))
      (node (ref "U4") (pin "P$14") (pinfunction "CBUS1_P$14") (pintype "bidirectional"))
    )
    (net (code "69") (name "Net-(U4-CBUS3)") (class "Default")
      (node (ref "R6") (pin "1") (pinfunction "1_1") (pintype "passive"))
      (node (ref "R7") (pin "2") (pinfunction "2_2") (pintype "passive"))
      (node (ref "R8") (pin "1") (pinfunction "1_1") (pintype "passive"))
      (node (ref "U4") (pin "P$16") (pinfunction "CBUS3_P$16") (pintype "bidirectional"))
    )
    (net (code "70") (name "Net-(U4-USBDM)") (class "Default")
      (node (ref "R5") (pin "2") (pinfunction "2_2") (pintype "passive"))
      (node (ref "U4") (pin "P$9") (pinfunction "USBDM_P$9") (pintype "bidirectional"))
    )
    (net (code "71") (name "Net-(U4-USBDP)") (class "Default")
      (node (ref "R4") (pin "2") (pinfunction "2_2") (pintype "passive"))
      (node (ref "U4") (pin "P$8") (pinfunction "USBDP_P$8") (pintype "bidirectional"))
    )
    (net (code "72") (name "unconnected-(U2-BYP-Pad4)") (class "Default")
      (node (ref "U2") (pin "4") (pinfunction "BYP_4") (pintype "no_connect"))
    )
    (net (code "73") (name "unconnected-(U3-BYP-Pad4)") (class "Default")
      (node (ref "U3") (pin "4") (pinfunction "BYP_4") (pintype "no_connect"))
    )
    (net (code "74") (name "unconnected-(U4-CBUS2-PadP$7)") (class "Default")
      (node (ref "U4") (pin "P$7") (pinfunction "CBUS2_P$7") (pintype "bidirectional"))
    )
    (net (code "75") (name "unconnected-(USB1B-USBID-PadID)") (class "Default")
      (node (ref "USB1") (pin "ID") (pinfunction "USBID_ID") (pintype "bidirectional"))
    )
  )
)
